# AD5933_breakout.net
KiCad netlist of a schematic drawn in EAGLE
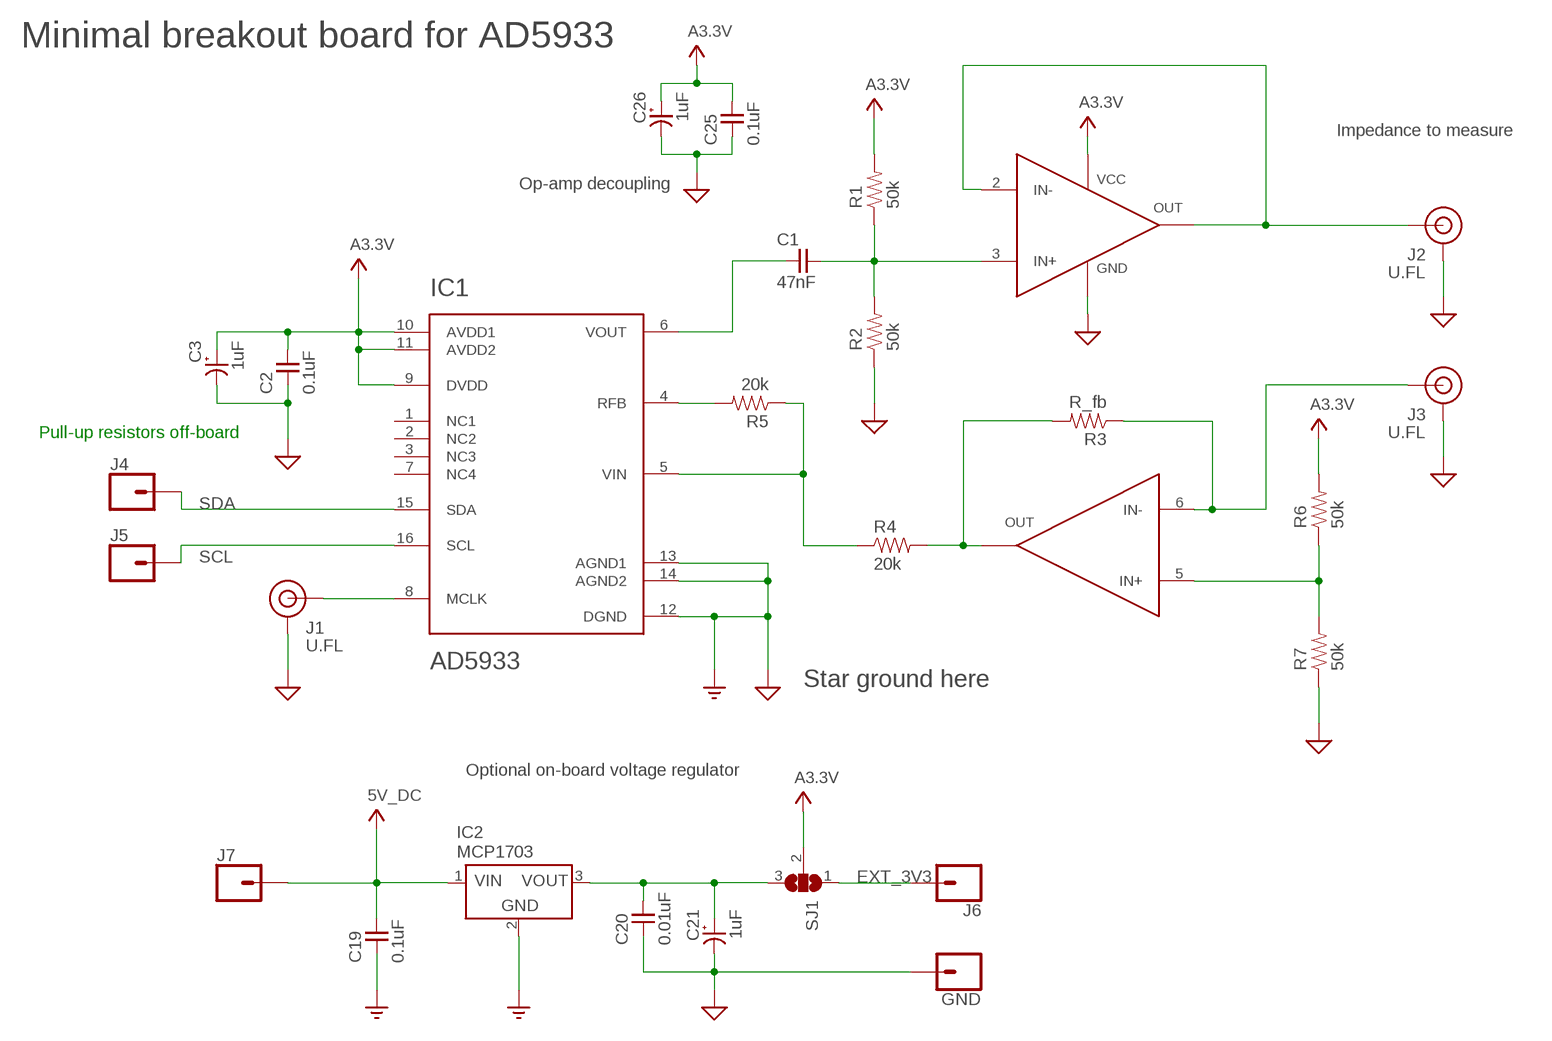
[diagram p0: schematic, sheet 1]

(export (version "E")
  (design (tool "Eeschema 10.0.6"))
  (components
    (comp (ref "C1")
      (value "47nF")
      (footprint "eagle-import:0805")
      (libsource (lib "eagle-import") (part "CAPACITOR0805"))
    )
    (comp (ref "C2")
      (value "0.1uF")
      (footprint "eagle-import:0805")
      (libsource (lib "eagle-import") (part "CAPACITOR0805"))
    )
    (comp (ref "C3")
      (value "1uF")
      (footprint "eagle-import:1206")
      (libsource (lib "eagle-import") (part "CAPACITOR+"))
    )
    (comp (ref "C19")
      (value "0.1uF")
      (footprint "eagle-import:0805")
      (libsource (lib "eagle-import") (part "CAPACITOR0805"))
    )
    (comp (ref "C20")
      (value "0.01uF")
      (footprint "eagle-import:0805")
      (libsource (lib "eagle-import") (part "CAPACITOR0805"))
    )
    (comp (ref "C21")
      (value "1uF")
      (footprint "eagle-import:1206")
      (libsource (lib "eagle-import") (part "CAPACITOR+"))
    )
    (comp (ref "C25")
      (value "0.1uF")
      (footprint "eagle-import:0805")
      (libsource (lib "eagle-import") (part "CAPACITOR0805"))
    )
    (comp (ref "C26")
      (value "1uF")
      (footprint "eagle-import:1206")
      (libsource (lib "eagle-import") (part "CAPACITOR+"))
    )
    (comp (ref "GND")
      (value "CONN_01PTH_NO_SILK_YES_STOP")
      (footprint "eagle-import:1X01_NO_SILK")
      (libsource (lib "eagle-import") (part "CONN_01PTH_NO_SILK_YES_STOP"))
    )
    (comp (ref "IC1")
      (value "AD5933")
      (footprint "eagle-import:SSOP_16")
      (libsource (lib "eagle-import") (part "AD5933"))
    )
    (comp (ref "IC2")
      (value "MCP1703")
      (footprint "eagle-import:SOT-23A")
      (libsource (lib "eagle-import") (part "MCP1703"))
    )
    (comp (ref "IC8")
      (value "AD8606SOIC_8")
      (footprint "eagle-import:SO_8")
      (libsource (lib "eagle-import") (part "AD8606SOIC_8"))
    )
    (comp (ref "J1")
      (value "U.FL")
      (footprint "eagle-import:U.FL")
      (libsource (lib "eagle-import") (part "U.FL2PIN"))
    )
    (comp (ref "J2")
      (value "U.FL")
      (footprint "eagle-import:U.FL")
      (libsource (lib "eagle-import") (part "U.FL2PIN"))
    )
    (comp (ref "J3")
      (value "U.FL")
      (footprint "eagle-import:U.FL")
      (libsource (lib "eagle-import") (part "U.FL2PIN"))
    )
    (comp (ref "J4")
      (value "CONN_01PTH_NO_SILK_YES_STOP")
      (footprint "eagle-import:1X01_NO_SILK")
      (libsource (lib "eagle-import") (part "CONN_01PTH_NO_SILK_YES_STOP"))
    )
    (comp (ref "J5")
      (value "CONN_01PTH_NO_SILK_YES_STOP")
      (footprint "eagle-import:1X01_NO_SILK")
      (libsource (lib "eagle-import") (part "CONN_01PTH_NO_SILK_YES_STOP"))
    )
    (comp (ref "J6")
      (value "CONN_01PTH_NO_SILK_YES_STOP")
      (footprint "eagle-import:1X01_NO_SILK")
      (libsource (lib "eagle-import") (part "CONN_01PTH_NO_SILK_YES_STOP"))
    )
    (comp (ref "J7")
      (value "CONN_01PTH_NO_SILK_YES_STOP")
      (footprint "eagle-import:1X01_NO_SILK")
      (libsource (lib "eagle-import") (part "CONN_01PTH_NO_SILK_YES_STOP"))
    )
    (comp (ref "R1")
      (value "50k")
      (footprint "eagle-import:0805")
      (libsource (lib "eagle-import") (part "RESISTOR0805SMD"))
    )
    (comp (ref "R2")
      (value "50k")
      (footprint "eagle-import:0805")
      (libsource (lib "eagle-import") (part "RESISTOR0805SMD"))
    )
    (comp (ref "R3")
      (value "R_fb")
      (footprint "eagle-import:0805")
      (libsource (lib "eagle-import") (part "RESISTOR0805SMD"))
    )
    (comp (ref "R4")
      (value "20k")
      (footprint "eagle-import:0805")
      (libsource (lib "eagle-import") (part "RESISTOR0805SMD"))
    )
    (comp (ref "R5")
      (value "20k")
      (footprint "eagle-import:0805")
      (libsource (lib "eagle-import") (part "RESISTOR0805SMD"))
    )
    (comp (ref "R6")
      (value "50k")
      (footprint "eagle-import:0805")
      (libsource (lib "eagle-import") (part "RESISTOR0805SMD"))
    )
    (comp (ref "R7")
      (value "50k")
      (footprint "eagle-import:0805")
      (libsource (lib "eagle-import") (part "RESISTOR0805SMD"))
    )
    (comp (ref "SJ1")
      (value "SJ2W")
      (footprint "eagle-import:SJ_2")
      (libsource (lib "eagle-import") (part "SJ2W"))
    )
  )
  (nets
    (net (code "1") (name "/EXT_3V3") (class "Default")
      (node (ref "J6") (pin "1") (pinfunction "1_1") (pintype "passive"))
      (node (ref "SJ1") (pin "1") (pinfunction "1_1") (pintype "passive"))
    )
    (net (code "2") (name "/SCL") (class "Default")
      (node (ref "IC1") (pin "16") (pinfunction "SCL_16") (pintype "bidirectional"))
      (node (ref "J5") (pin "1") (pinfunction "1_1") (pintype "passive"))
    )
    (net (code "3") (name "/SDA") (class "Default")
      (node (ref "IC1") (pin "15") (pinfunction "SDA_15") (pintype "bidirectional"))
      (node (ref "J4") (pin "1") (pinfunction "1_1") (pintype "passive"))
    )
    (net (code "4") (name "5V_DC") (class "Default")
      (node (ref "C19") (pin "2") (pinfunction "2_2") (pintype "passive"))
      (node (ref "IC2") (pin "1") (pinfunction "VIN_1") (pintype "power_in"))
      (node (ref "J7") (pin "1") (pinfunction "1_1") (pintype "passive"))
    )
    (net (code "5") (name "A3.3V") (class "Default")
      (node (ref "C2") (pin "2") (pinfunction "2_2") (pintype "passive"))
      (node (ref "C25") (pin "2") (pinfunction "2_2") (pintype "passive"))
      (node (ref "C26") (pin "1") (pinfunction "1_1") (pintype "passive"))
      (node (ref "C3") (pin "1") (pinfunction "1_1") (pintype "passive"))
      (node (ref "IC1") (pin "10") (pinfunction "AVDD1_10") (pintype "bidirectional"))
      (node (ref "IC1") (pin "11") (pinfunction "AVDD2_11") (pintype "bidirectional"))
      (node (ref "IC1") (pin "9") (pinfunction "DVDD_9") (pintype "bidirectional"))
      (node (ref "IC8") (pin "8") (pinfunction "VCC_8") (pintype "bidirectional"))
      (node (ref "R1") (pin "2") (pinfunction "2_2") (pintype "passive"))
      (node (ref "R6") (pin "2") (pinfunction "2_2") (pintype "passive"))
      (node (ref "SJ1") (pin "2") (pinfunction "2_2") (pintype "passive"))
    )
    (net (code "6") (name "AGND") (class "Default")
      (node (ref "C19") (pin "1") (pinfunction "1_1") (pintype "passive"))
      (node (ref "C2") (pin "1") (pinfunction "1_1") (pintype "passive"))
      (node (ref "C20") (pin "1") (pinfunction "1_1") (pintype "passive"))
      (node (ref "C21") (pin "2") (pinfunction "2_2") (pintype "passive"))
      (node (ref "C25") (pin "1") (pinfunction "1_1") (pintype "passive"))
      (node (ref "C26") (pin "2") (pinfunction "2_2") (pintype "passive"))
      (node (ref "C3") (pin "2") (pinfunction "2_2") (pintype "passive"))
      (node (ref "GND") (pin "1") (pinfunction "1_1") (pintype "passive"))
      (node (ref "IC1") (pin "12") (pinfunction "DGND_12") (pintype "bidirectional"))
      (node (ref "IC1") (pin "13") (pinfunction "AGND1_13") (pintype "bidirectional"))
      (node (ref "IC1") (pin "14") (pinfunction "AGND2_14") (pintype "bidirectional"))
      (node (ref "IC2") (pin "2") (pinfunction "GND_2") (pintype "power_in"))
      (node (ref "IC8") (pin "4") (pinfunction "GND_4") (pintype "bidirectional"))
      (node (ref "J1") (pin "1") (pinfunction "GND_1") (pintype "bidirectional"))
      (node (ref "J1") (pin "2") (pinfunction "GND_2") (pintype "bidirectional"))
      (node (ref "J2") (pin "1") (pinfunction "GND_1") (pintype "bidirectional"))
      (node (ref "J2") (pin "2") (pinfunction "GND_2") (pintype "bidirectional"))
      (node (ref "J3") (pin "1") (pinfunction "GND_1") (pintype "bidirectional"))
      (node (ref "J3") (pin "2") (pinfunction "GND_2") (pintype "bidirectional"))
      (node (ref "R2") (pin "1") (pinfunction "1_1") (pintype "passive"))
      (node (ref "R7") (pin "1") (pinfunction "1_1") (pintype "passive"))
    )
    (net (code "7") (name "Net-(IC1-MCLK)") (class "Default")
      (node (ref "IC1") (pin "8") (pinfunction "MCLK_8") (pintype "bidirectional"))
      (node (ref "J1") (pin "FEED") (pinfunction "SIGNAL_FEED") (pintype "bidirectional"))
    )
    (net (code "8") (name "Net-(IC1-RFB)") (class "Default")
      (node (ref "IC1") (pin "4") (pinfunction "RFB_4") (pintype "bidirectional"))
      (node (ref "R5") (pin "2") (pinfunction "2_2") (pintype "passive"))
    )
    (net (code "9") (name "Net-(IC1-VIN)") (class "Default")
      (node (ref "IC1") (pin "5") (pinfunction "VIN_5") (pintype "bidirectional"))
      (node (ref "R4") (pin "1") (pinfunction "1_1") (pintype "passive"))
      (node (ref "R5") (pin "1") (pinfunction "1_1") (pintype "passive"))
    )
    (net (code "10") (name "Net-(IC1-VOUT)") (class "Default")
      (node (ref "C1") (pin "1") (pinfunction "1_1") (pintype "passive"))
      (node (ref "IC1") (pin "6") (pinfunction "VOUT_6") (pintype "bidirectional"))
    )
    (net (code "11") (name "Net-(IC2-VOUT)") (class "Default")
      (node (ref "C20") (pin "2") (pinfunction "2_2") (pintype "passive"))
      (node (ref "C21") (pin "1") (pinfunction "1_1") (pintype "passive"))
      (node (ref "IC2") (pin "3") (pinfunction "VOUT_3") (pintype "power_in"))
      (node (ref "SJ1") (pin "3") (pinfunction "3_3") (pintype "passive"))
    )
    (net (code "12") (name "Net-(IC8A-IN+)") (class "Default")
      (node (ref "C1") (pin "2") (pinfunction "2_2") (pintype "passive"))
      (node (ref "IC8") (pin "3") (pinfunction "IN+_3") (pintype "bidirectional"))
      (node (ref "R1") (pin "1") (pinfunction "1_1") (pintype "passive"))
      (node (ref "R2") (pin "2") (pinfunction "2_2") (pintype "passive"))
    )
    (net (code "13") (name "Net-(IC8A-IN-)") (class "Default")
      (node (ref "IC8") (pin "1") (pinfunction "OUT_1") (pintype "bidirectional"))
      (node (ref "IC8") (pin "2") (pinfunction "IN-_2") (pintype "bidirectional"))
      (node (ref "J2") (pin "FEED") (pinfunction "SIGNAL_FEED") (pintype "bidirectional"))
    )
    (net (code "14") (name "Net-(IC8B-IN+)") (class "Default")
      (node (ref "IC8") (pin "5") (pinfunction "IN+_5") (pintype "bidirectional"))
      (node (ref "R6") (pin "1") (pinfunction "1_1") (pintype "passive"))
      (node (ref "R7") (pin "2") (pinfunction "2_2") (pintype "passive"))
    )
    (net (code "15") (name "Net-(IC8B-IN-)") (class "Default")
      (node (ref "IC8") (pin "6") (pinfunction "IN-_6") (pintype "bidirectional"))
      (node (ref "J3") (pin "FEED") (pinfunction "SIGNAL_FEED") (pintype "bidirectional"))
      (node (ref "R3") (pin "1") (pinfunction "1_1") (pintype "passive"))
    )
    (net (code "16") (name "Net-(IC8B-OUT)") (class "Default")
      (node (ref "IC8") (pin "7") (pinfunction "OUT_7") (pintype "bidirectional"))
      (node (ref "R3") (pin "2") (pinfunction "2_2") (pintype "passive"))
      (node (ref "R4") (pin "2") (pinfunction "2_2") (pintype "passive"))
    )
    (net (code "17") (name "unconnected-(IC1-NC1-Pad1)") (class "Default")
      (node (ref "IC1") (pin "1") (pinfunction "NC1_1") (pintype "no_connect"))
    )
    (net (code "18") (name "unconnected-(IC1-NC2-Pad2)") (class "Default")
      (node (ref "IC1") (pin "2") (pinfunction "NC2_2") (pintype "no_connect"))
    )
    (net (code "19") (name "unconnected-(IC1-NC3-Pad3)") (class "Default")
      (node (ref "IC1") (pin "3") (pinfunction "NC3_3") (pintype "no_connect"))
    )
    (net (code "20") (name "unconnected-(IC1-NC4-Pad7)") (class "Default")
      (node (ref "IC1") (pin "7") (pinfunction "NC4_7") (pintype "no_connect"))
    )
  )
)
